# ADS8588.net
KiCad netlist of a schematic drawn in Altium Designer
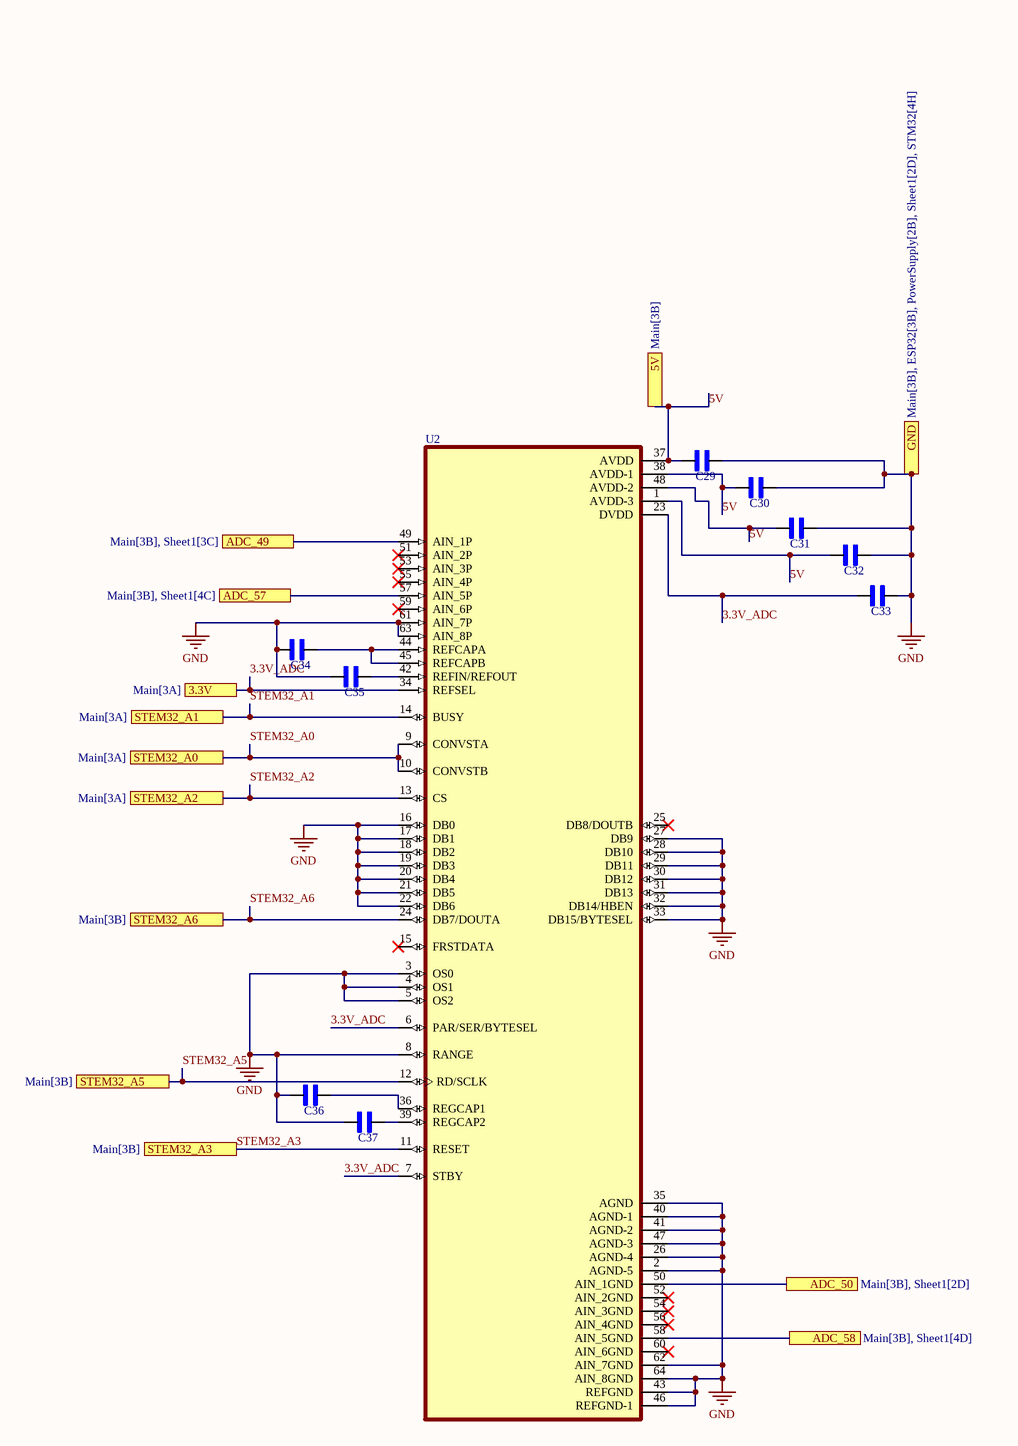
[diagram p0: ADS8588.SchDoc]

(export (version "E")
  (design (tool "Eeschema 10.0.6"))
  (components
    (comp (ref "C29")
      (value "CAP603")
      (footprint "CAP603")
      (description "0.1 ÂµF Â±5% 10V Ceramic Capacitor X7R 0603 (1608 Metric)")
      (fields (field (name "MF") "Vishay") (field (name "MP") "VJ0603Y104JXQCW1BC"))
      (libsource (lib "ESP32-S3-WROOM-1-N16R8") (part "CAP603"))
    )
    (comp (ref "C30")
      (value "CAP603")
      (footprint "CAP603")
      (description "0.1 ÂµF Â±5% 10V Ceramic Capacitor X7R 0603 (1608 Metric)")
      (fields (field (name "MF") "Vishay") (field (name "MP") "VJ0603Y104JXQCW1BC"))
      (libsource (lib "ESP32-S3-WROOM-1-N16R8") (part "CAP603"))
    )
    (comp (ref "C31")
      (value "CAP603")
      (footprint "CAP603")
      (description "0.1 ÂµF Â±5% 10V Ceramic Capacitor X7R 0603 (1608 Metric)")
      (fields (field (name "MF") "Vishay") (field (name "MP") "VJ0603Y104JXQCW1BC"))
      (libsource (lib "ESP32-S3-WROOM-1-N16R8") (part "CAP603"))
    )
    (comp (ref "C32")
      (value "CAP603")
      (footprint "CAP603")
      (description "0.1 ÂµF Â±5% 10V Ceramic Capacitor X7R 0603 (1608 Metric)")
      (fields (field (name "MF") "Vishay") (field (name "MP") "VJ0603Y104JXQCW1BC"))
      (libsource (lib "ESP32-S3-WROOM-1-N16R8") (part "CAP603"))
    )
    (comp (ref "C33")
      (value "CAP603")
      (footprint "CAP603")
      (description "0.1 ÂµF Â±5% 10V Ceramic Capacitor X7R 0603 (1608 Metric)")
      (fields (field (name "MF") "Vishay") (field (name "MP") "VJ0603Y104JXQCW1BC"))
      (libsource (lib "ESP32-S3-WROOM-1-N16R8") (part "CAP603"))
    )
    (comp (ref "C34")
      (value "CAP603")
      (footprint "CAP603")
      (description "0.1 ÂµF Â±5% 10V Ceramic Capacitor X7R 0603 (1608 Metric)")
      (fields (field (name "MF") "Vishay") (field (name "MP") "VJ0603Y104JXQCW1BC"))
      (libsource (lib "ESP32-S3-WROOM-1-N16R8") (part "CAP603"))
    )
    (comp (ref "C35")
      (value "CAP603")
      (footprint "CAP603")
      (description "0.1 ÂµF Â±5% 10V Ceramic Capacitor X7R 0603 (1608 Metric)")
      (fields (field (name "MF") "Vishay") (field (name "MP") "VJ0603Y104JXQCW1BC"))
      (libsource (lib "ESP32-S3-WROOM-1-N16R8") (part "CAP603"))
    )
    (comp (ref "C36")
      (value "CAP603")
      (footprint "CAP603")
      (description "0.1 ÂµF Â±5% 10V Ceramic Capacitor X7R 0603 (1608 Metric)")
      (fields (field (name "MF") "Vishay") (field (name "MP") "VJ0603Y104JXQCW1BC"))
      (libsource (lib "ESP32-S3-WROOM-1-N16R8") (part "CAP603"))
    )
    (comp (ref "C37")
      (value "CAP603")
      (footprint "CAP603")
      (description "0.1 ÂµF Â±5% 10V Ceramic Capacitor X7R 0603 (1608 Metric)")
      (fields (field (name "MF") "Vishay") (field (name "MP") "VJ0603Y104JXQCW1BC"))
      (libsource (lib "ESP32-S3-WROOM-1-N16R8") (part "CAP603"))
    )
    (comp (ref "U2")
      (value "ADS8588SIPM")
      (footprint "ADS8588SIPM")
      (fields (field (name "MF") "Texas Instruments"))
      (libsource (lib "ESP32-S3-WROOM-1-N16R8") (part "ADS8588SIPM"))
    )
  )
  (nets
    (net (code "1") (name "/3.3V_ADC") (class "Default")
      (node (ref "C33") (pin "1") (pinfunction "1_1") (pintype "passive"))
      (node (ref "U2") (pin "23") (pinfunction "DVDD_23") (pintype "power_in"))
      (node (ref "U2") (pin "34") (pinfunction "REFSEL_34") (pintype "input"))
      (node (ref "U2") (pin "6") (pinfunction "PAR/SER/BYTESEL_6") (pintype "bidirectional"))
      (node (ref "U2") (pin "7") (pinfunction "STBY_7") (pintype "bidirectional"))
    )
    (net (code "2") (name "/5V") (class "Default")
      (node (ref "C29") (pin "1") (pinfunction "1_1") (pintype "passive"))
      (node (ref "C30") (pin "1") (pinfunction "1_1") (pintype "passive"))
      (node (ref "C31") (pin "1") (pinfunction "1_1") (pintype "passive"))
      (node (ref "C32") (pin "1") (pinfunction "1_1") (pintype "passive"))
      (node (ref "U2") (pin "1") (pinfunction "AVDD-3_1") (pintype "power_in"))
      (node (ref "U2") (pin "37") (pinfunction "AVDD_37") (pintype "power_in"))
      (node (ref "U2") (pin "38") (pinfunction "AVDD-1_38") (pintype "power_in"))
      (node (ref "U2") (pin "48") (pinfunction "AVDD-2_48") (pintype "power_in"))
    )
    (net (code "3") (name "/ADC_49") (class "Default")
      (node (ref "U2") (pin "49") (pinfunction "AIN_1P_49") (pintype "input"))
    )
    (net (code "4") (name "/ADC_50") (class "Default")
      (node (ref "U2") (pin "50") (pinfunction "AIN_1GND_50") (pintype "power_in"))
    )
    (net (code "5") (name "/ADC_57") (class "Default")
      (node (ref "U2") (pin "57") (pinfunction "AIN_5P_57") (pintype "input"))
    )
    (net (code "6") (name "/ADC_58") (class "Default")
      (node (ref "U2") (pin "58") (pinfunction "AIN_5GND_58") (pintype "power_in"))
    )
    (net (code "7") (name "/STEM32_A0") (class "Default")
      (node (ref "U2") (pin "10") (pinfunction "CONVSTB_10") (pintype "bidirectional"))
      (node (ref "U2") (pin "9") (pinfunction "CONVSTA_9") (pintype "bidirectional"))
    )
    (net (code "8") (name "/STEM32_A1") (class "Default")
      (node (ref "U2") (pin "14") (pinfunction "BUSY_14") (pintype "bidirectional"))
    )
    (net (code "9") (name "/STEM32_A2") (class "Default")
      (node (ref "U2") (pin "13") (pinfunction "CS_13") (pintype "bidirectional"))
    )
    (net (code "10") (name "/STEM32_A3") (class "Default")
      (node (ref "U2") (pin "11") (pinfunction "RESET_11") (pintype "bidirectional"))
    )
    (net (code "11") (name "/STEM32_A5") (class "Default")
      (node (ref "U2") (pin "12") (pinfunction "RD/SCLK_12") (pintype "bidirectional"))
    )
    (net (code "12") (name "/STEM32_A6") (class "Default")
      (node (ref "U2") (pin "24") (pinfunction "DB7/DOUTA_24") (pintype "bidirectional"))
    )
    (net (code "13") (name "GND") (class "Default")
      (node (ref "C29") (pin "2") (pinfunction "2_2") (pintype "passive"))
      (node (ref "C30") (pin "2") (pinfunction "2_2") (pintype "passive"))
      (node (ref "C31") (pin "2") (pinfunction "2_2") (pintype "passive"))
      (node (ref "C32") (pin "2") (pinfunction "2_2") (pintype "passive"))
      (node (ref "C33") (pin "2") (pinfunction "2_2") (pintype "passive"))
      (node (ref "C34") (pin "1") (pinfunction "1_1") (pintype "passive"))
      (node (ref "C35") (pin "1") (pinfunction "1_1") (pintype "passive"))
      (node (ref "C36") (pin "1") (pinfunction "1_1") (pintype "passive"))
      (node (ref "C37") (pin "1") (pinfunction "1_1") (pintype "passive"))
      (node (ref "U2") (pin "16") (pinfunction "DB0_16") (pintype "bidirectional"))
      (node (ref "U2") (pin "17") (pinfunction "DB1_17") (pintype "bidirectional"))
      (node (ref "U2") (pin "18") (pinfunction "DB2_18") (pintype "bidirectional"))
      (node (ref "U2") (pin "19") (pinfunction "DB3_19") (pintype "bidirectional"))
      (node (ref "U2") (pin "2") (pinfunction "AGND-5_2") (pintype "power_in"))
      (node (ref "U2") (pin "20") (pinfunction "DB4_20") (pintype "bidirectional"))
      (node (ref "U2") (pin "21") (pinfunction "DB5_21") (pintype "bidirectional"))
      (node (ref "U2") (pin "22") (pinfunction "DB6_22") (pintype "bidirectional"))
      (node (ref "U2") (pin "26") (pinfunction "AGND-4_26") (pintype "power_in"))
      (node (ref "U2") (pin "27") (pinfunction "DB9_27") (pintype "bidirectional"))
      (node (ref "U2") (pin "28") (pinfunction "DB10_28") (pintype "bidirectional"))
      (node (ref "U2") (pin "29") (pinfunction "DB11_29") (pintype "bidirectional"))
      (node (ref "U2") (pin "3") (pinfunction "OS0_3") (pintype "bidirectional"))
      (node (ref "U2") (pin "30") (pinfunction "DB12_30") (pintype "bidirectional"))
      (node (ref "U2") (pin "31") (pinfunction "DB13_31") (pintype "bidirectional"))
      (node (ref "U2") (pin "32") (pinfunction "DB14/HBEN_32") (pintype "bidirectional"))
      (node (ref "U2") (pin "33") (pinfunction "DB15/BYTESEL_33") (pintype "bidirectional"))
      (node (ref "U2") (pin "35") (pinfunction "AGND_35") (pintype "power_in"))
      (node (ref "U2") (pin "4") (pinfunction "OS1_4") (pintype "bidirectional"))
      (node (ref "U2") (pin "40") (pinfunction "AGND-1_40") (pintype "power_in"))
      (node (ref "U2") (pin "41") (pinfunction "AGND-2_41") (pintype "power_in"))
      (node (ref "U2") (pin "43") (pinfunction "REFGND_43") (pintype "power_in"))
      (node (ref "U2") (pin "46") (pinfunction "REFGND-1_46") (pintype "power_in"))
      (node (ref "U2") (pin "47") (pinfunction "AGND-3_47") (pintype "power_in"))
      (node (ref "U2") (pin "5") (pinfunction "OS2_5") (pintype "bidirectional"))
      (node (ref "U2") (pin "61") (pinfunction "AIN_7P_61") (pintype "input"))
      (node (ref "U2") (pin "62") (pinfunction "AIN_7GND_62") (pintype "power_in"))
      (node (ref "U2") (pin "63") (pinfunction "AIN_8P_63") (pintype "input"))
      (node (ref "U2") (pin "64") (pinfunction "AIN_8GND_64") (pintype "power_in"))
      (node (ref "U2") (pin "8") (pinfunction "RANGE_8") (pintype "bidirectional"))
    )
    (net (code "14") (name "Net-(U2-REFCAPA)") (class "Default")
      (node (ref "C34") (pin "2") (pinfunction "2_2") (pintype "passive"))
      (node (ref "U2") (pin "44") (pinfunction "REFCAPA_44") (pintype "input"))
      (node (ref "U2") (pin "45") (pinfunction "REFCAPB_45") (pintype "input"))
    )
    (net (code "15") (name "Net-(U2-REFIN{slash}REFOUT)") (class "Default")
      (node (ref "C35") (pin "2") (pinfunction "2_2") (pintype "passive"))
      (node (ref "U2") (pin "42") (pinfunction "REFIN/REFOUT_42") (pintype "input"))
    )
    (net (code "16") (name "Net-(U2-REGCAP1)") (class "Default")
      (node (ref "C36") (pin "2") (pinfunction "2_2") (pintype "passive"))
      (node (ref "U2") (pin "36") (pinfunction "REGCAP1_36") (pintype "bidirectional"))
    )
    (net (code "17") (name "Net-(U2-REGCAP2)") (class "Default")
      (node (ref "C37") (pin "2") (pinfunction "2_2") (pintype "passive"))
      (node (ref "U2") (pin "39") (pinfunction "REGCAP2_39") (pintype "bidirectional"))
    )
    (net (code "18") (name "unconnected-(U2-AIN_2GND-Pad52)") (class "Default")
      (node (ref "U2") (pin "52") (pinfunction "AIN_2GND_52") (pintype "power_in+no_connect"))
    )
    (net (code "19") (name "unconnected-(U2-AIN_2P-Pad51)") (class "Default")
      (node (ref "U2") (pin "51") (pinfunction "AIN_2P_51") (pintype "input+no_connect"))
    )
    (net (code "20") (name "unconnected-(U2-AIN_3GND-Pad54)") (class "Default")
      (node (ref "U2") (pin "54") (pinfunction "AIN_3GND_54") (pintype "power_in+no_connect"))
    )
    (net (code "21") (name "unconnected-(U2-AIN_3P-Pad53)") (class "Default")
      (node (ref "U2") (pin "53") (pinfunction "AIN_3P_53") (pintype "input+no_connect"))
    )
    (net (code "22") (name "unconnected-(U2-AIN_4GND-Pad56)") (class "Default")
      (node (ref "U2") (pin "56") (pinfunction "AIN_4GND_56") (pintype "power_in+no_connect"))
    )
    (net (code "23") (name "unconnected-(U2-AIN_4P-Pad55)") (class "Default")
      (node (ref "U2") (pin "55") (pinfunction "AIN_4P_55") (pintype "input+no_connect"))
    )
    (net (code "24") (name "unconnected-(U2-AIN_6GND-Pad60)") (class "Default")
      (node (ref "U2") (pin "60") (pinfunction "AIN_6GND_60") (pintype "power_in+no_connect"))
    )
    (net (code "25") (name "unconnected-(U2-AIN_6P-Pad59)") (class "Default")
      (node (ref "U2") (pin "59") (pinfunction "AIN_6P_59") (pintype "input+no_connect"))
    )
    (net (code "26") (name "unconnected-(U2-DB8{slash}DOUTB-Pad25)") (class "Default")
      (node (ref "U2") (pin "25") (pinfunction "DB8/DOUTB_25") (pintype "bidirectional+no_connect"))
    )
    (net (code "27") (name "unconnected-(U2-FRSTDATA-Pad15)") (class "Default")
      (node (ref "U2") (pin "15") (pinfunction "FRSTDATA_15") (pintype "bidirectional+no_connect"))
    )
  )
)
